# Adafruit_BME280.net
KiCad netlist of a schematic drawn in EAGLE
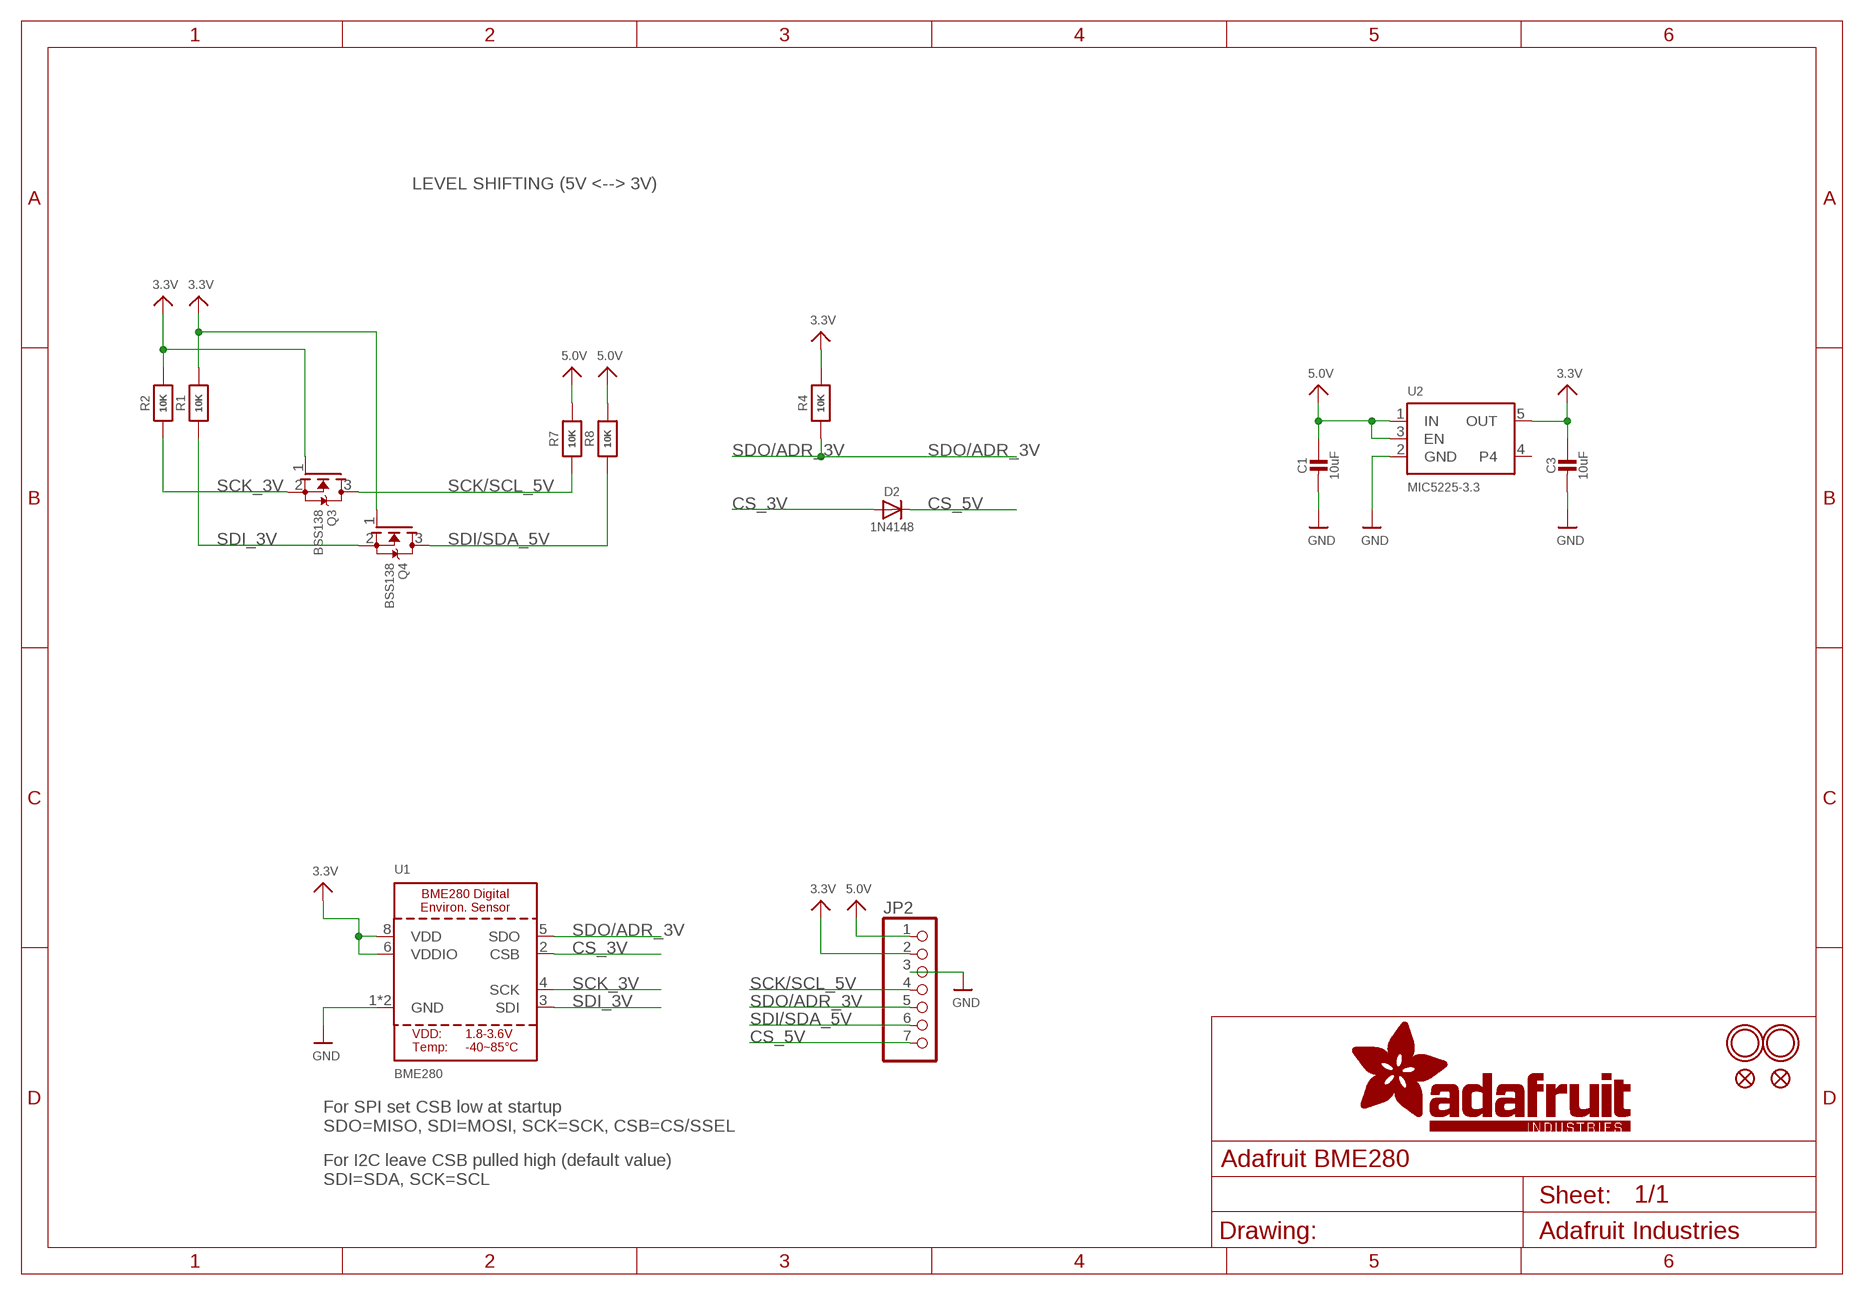
[diagram p0: schematic, sheet 1]

(export (version "E")
  (design (tool "Eeschema 10.0.6"))
  (components
    (comp (ref "C1")
      (value "10uF")
      (footprint "eagle-import:0805-NO")
      (libsource (lib "eagle-import") (part "CAP_CERAMIC0805-NOOUTLINE"))
    )
    (comp (ref "C3")
      (value "10uF")
      (footprint "eagle-import:0805-NO")
      (libsource (lib "eagle-import") (part "CAP_CERAMIC0805-NOOUTLINE"))
    )
    (comp (ref "D2")
      (value "1N4148")
      (footprint "eagle-import:SOD-323")
      (libsource (lib "eagle-import") (part "DIODESOD-323"))
    )
    (comp (ref "JP2")
      (value "HEADER-1X770MIL")
      (footprint "eagle-import:1X07_ROUND_70")
      (libsource (lib "eagle-import") (part "HEADER-1X770MIL"))
    )
    (comp (ref "Q3")
      (value "BSS138")
      (footprint "eagle-import:SOT23-WIDE")
      (libsource (lib "eagle-import") (part "MOSFET-NWIDE"))
    )
    (comp (ref "Q4")
      (value "BSS138")
      (footprint "eagle-import:SOT23-WIDE")
      (libsource (lib "eagle-import") (part "MOSFET-NWIDE"))
    )
    (comp (ref "R1")
      (value "10K")
      (footprint "eagle-import:0805-NO")
      (libsource (lib "eagle-import") (part "RESISTOR0805_NOOUTLINE"))
    )
    (comp (ref "R2")
      (value "10K")
      (footprint "eagle-import:0805-NO")
      (libsource (lib "eagle-import") (part "RESISTOR0805_NOOUTLINE"))
    )
    (comp (ref "R4")
      (value "10K")
      (footprint "eagle-import:_0805MP")
      (libsource (lib "eagle-import") (part "RESISTOR_0805MP"))
    )
    (comp (ref "R7")
      (value "10K")
      (footprint "eagle-import:0805-NO")
      (libsource (lib "eagle-import") (part "RESISTOR0805_NOOUTLINE"))
    )
    (comp (ref "R8")
      (value "10K")
      (footprint "eagle-import:0805-NO")
      (libsource (lib "eagle-import") (part "RESISTOR0805_NOOUTLINE"))
    )
    (comp (ref "U$5")
      (value "FIDUCIAL\"\"")
      (footprint "eagle-import:FIDUCIAL_1MM")
      (libsource (lib "eagle-import") (part "FIDUCIAL{dblquote}{dblquote}"))
    )
    (comp (ref "U$7")
      (value "MOUNTINGHOLE2.0")
      (footprint "eagle-import:MOUNTINGHOLE_2.0_PLATED")
      (libsource (lib "eagle-import") (part "MOUNTINGHOLE2.0"))
    )
    (comp (ref "U$8")
      (value "MOUNTINGHOLE2.0")
      (footprint "eagle-import:MOUNTINGHOLE_2.0_PLATED")
      (libsource (lib "eagle-import") (part "MOUNTINGHOLE2.0"))
    )
    (comp (ref "U$15")
      (value "FIDUCIAL\"\"")
      (footprint "eagle-import:FIDUCIAL_1MM")
      (libsource (lib "eagle-import") (part "FIDUCIAL{dblquote}{dblquote}"))
    )
    (comp (ref "U1")
      (value "BME280")
      (footprint "eagle-import:BME280")
      (libsource (lib "eagle-import") (part "BME280"))
    )
    (comp (ref "U2")
      (value "MIC5225-3.3")
      (footprint "eagle-import:SOT23-5")
      (libsource (lib "eagle-import") (part "VREG_SOT23-5"))
    )
  )
  (nets
    (net (code "1") (name "/CS_3V") (class "Default")
      (node (ref "D2") (pin "A") (pinfunction "A_A") (pintype "passive"))
      (node (ref "U1") (pin "2") (pinfunction "CSB_2") (pintype "input"))
    )
    (net (code "2") (name "/CS_5V") (class "Default")
      (node (ref "D2") (pin "C") (pinfunction "C_C") (pintype "passive"))
      (node (ref "JP2") (pin "7") (pinfunction "7_7") (pintype "passive"))
    )
    (net (code "3") (name "/SCK_3V") (class "Default")
      (node (ref "Q3") (pin "2") (pinfunction "S_2") (pintype "bidirectional"))
      (node (ref "R2") (pin "1") (pinfunction "1_1") (pintype "passive"))
      (node (ref "U1") (pin "4") (pinfunction "SCK_4") (pintype "input"))
    )
    (net (code "4") (name "/SCK{slash}SCL_5V") (class "Default")
      (node (ref "JP2") (pin "4") (pinfunction "4_4") (pintype "passive"))
      (node (ref "Q3") (pin "3") (pinfunction "D_3") (pintype "bidirectional"))
      (node (ref "R7") (pin "1") (pinfunction "1_1") (pintype "passive"))
    )
    (net (code "5") (name "/SDI_3V") (class "Default")
      (node (ref "Q4") (pin "2") (pinfunction "S_2") (pintype "bidirectional"))
      (node (ref "R1") (pin "1") (pinfunction "1_1") (pintype "passive"))
      (node (ref "U1") (pin "3") (pinfunction "SDI_3") (pintype "input"))
    )
    (net (code "6") (name "/SDI{slash}SDA_5V") (class "Default")
      (node (ref "JP2") (pin "6") (pinfunction "6_6") (pintype "passive"))
      (node (ref "Q4") (pin "3") (pinfunction "D_3") (pintype "bidirectional"))
      (node (ref "R8") (pin "1") (pinfunction "1_1") (pintype "passive"))
    )
    (net (code "7") (name "/SDO{slash}ADR_3V") (class "Default")
      (node (ref "JP2") (pin "5") (pinfunction "5_5") (pintype "passive"))
      (node (ref "R4") (pin "1") (pinfunction "1_1") (pintype "passive"))
      (node (ref "U1") (pin "5") (pinfunction "SDO_5") (pintype "output"))
    )
    (net (code "8") (name "3.3V") (class "Default")
      (node (ref "C3") (pin "1") (pinfunction "1_1") (pintype "passive"))
      (node (ref "JP2") (pin "2") (pinfunction "2_2") (pintype "passive"))
      (node (ref "Q3") (pin "1") (pinfunction "G_1") (pintype "bidirectional"))
      (node (ref "Q4") (pin "1") (pinfunction "G_1") (pintype "bidirectional"))
      (node (ref "R1") (pin "2") (pinfunction "2_2") (pintype "passive"))
      (node (ref "R2") (pin "2") (pinfunction "2_2") (pintype "passive"))
      (node (ref "R4") (pin "2") (pinfunction "2_2") (pintype "passive"))
      (node (ref "U1") (pin "6") (pinfunction "VDDIO_6") (pintype "power_in"))
      (node (ref "U1") (pin "8") (pinfunction "VDD_8") (pintype "power_in"))
      (node (ref "U2") (pin "5") (pinfunction "OUT_5") (pintype "power_in"))
    )
    (net (code "9") (name "5.0V") (class "Default")
      (node (ref "C1") (pin "1") (pinfunction "1_1") (pintype "passive"))
      (node (ref "JP2") (pin "1") (pinfunction "1_1") (pintype "passive"))
      (node (ref "R7") (pin "2") (pinfunction "2_2") (pintype "passive"))
      (node (ref "R8") (pin "2") (pinfunction "2_2") (pintype "passive"))
      (node (ref "U2") (pin "1") (pinfunction "IN_1") (pintype "power_in"))
      (node (ref "U2") (pin "3") (pinfunction "EN_3") (pintype "input"))
    )
    (net (code "10") (name "GND") (class "Default")
      (node (ref "C1") (pin "2") (pinfunction "2_2") (pintype "passive"))
      (node (ref "C3") (pin "2") (pinfunction "2_2") (pintype "passive"))
      (node (ref "JP2") (pin "3") (pinfunction "3_3") (pintype "passive"))
      (node (ref "U1") (pin "1") (pinfunction "GND_1") (pintype "power_in"))
      (node (ref "U1") (pin "7") (pinfunction "GND_7") (pintype "power_in"))
      (node (ref "U2") (pin "2") (pinfunction "GND_2") (pintype "power_in"))
    )
    (net (code "11") (name "unconnected-(U2-P4-Pad4)") (class "Default")
      (node (ref "U2") (pin "4") (pinfunction "P4_4") (pintype "bidirectional"))
    )
  )
)
